# Power.net
KiCad netlist of a schematic drawn in Altium Designer
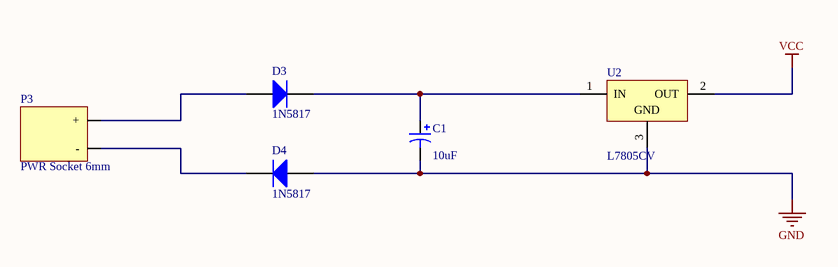
[diagram p0: Power.SchDoc]

(export (version "E")
  (design (tool "Eeschema 10.0.6"))
  (components
    (comp (ref "C1")
      (value "10uF")
      (footprint "CAPPR1.5-4x5")
      (description "Polarized Capacitor (Radial)")
      (fields (field (name "Comment") "Cap Pol1") (field (name "PUBLISHER") "Altium Limited"))
      (libsource (lib "Miscellaneous Devices") (part "Cap Pol1"))
    )
    (comp (ref "D3") (value "1N5817") (footprint "1N5817") (libsource (lib "Components") (part "1N5817")))
    (comp (ref "D4") (value "1N5817") (footprint "1N5817") (libsource (lib "Components") (part "1N5817")))
    (comp (ref "P3")
      (value "PWR Socket 6mm")
      (footprint "PWR Socket 6mm")
      (libsource (lib "Components") (part "PWR Socket 6mm"))
    )
    (comp (ref "U2")
      (value "L7805CV")
      (footprint "TO220ABN")
      (description "Positive Voltage Regulator")
      (fields (field (name "PUBLISHER") "Altium Limited"))
      (libsource (lib "ST Power Mgt Voltage Regulator") (part "L7805CV"))
    )
  )
  (nets
    (net (code "1") (name "GND") (class "Default")
      (node (ref "C1") (pin "2") (pinfunction "2_2") (pintype "passive"))
      (node (ref "D4") (pin "A") (pinfunction "A_A") (pintype "passive"))
      (node (ref "U2") (pin "3") (pinfunction "GND_3") (pintype "power_in"))
    )
    (net (code "2") (name "Net-(D3-PadA)") (class "Default")
      (node (ref "D3") (pin "A") (pinfunction "A_A") (pintype "passive"))
      (node (ref "P3") (pin "+") (pinfunction "+_+") (pintype "passive"))
    )
    (net (code "3") (name "Net-(D4-PadK)") (class "Default")
      (node (ref "D4") (pin "K") (pinfunction "K_K") (pintype "passive"))
      (node (ref "P3") (pin "-") (pinfunction "-_-") (pintype "passive"))
    )
    (net (code "4") (name "Net-(U2-IN)") (class "Default")
      (node (ref "C1") (pin "1") (pinfunction "1_1") (pintype "passive"))
      (node (ref "D3") (pin "K") (pinfunction "K_K") (pintype "passive"))
      (node (ref "U2") (pin "1") (pinfunction "IN_1") (pintype "power_in"))
    )
    (net (code "5") (name "VCC") (class "Default")
      (node (ref "U2") (pin "2") (pinfunction "OUT_2") (pintype "power_in"))
    )
  )
)
